# lpc11c14.net
KiCad netlist of a schematic drawn in Altium Designer
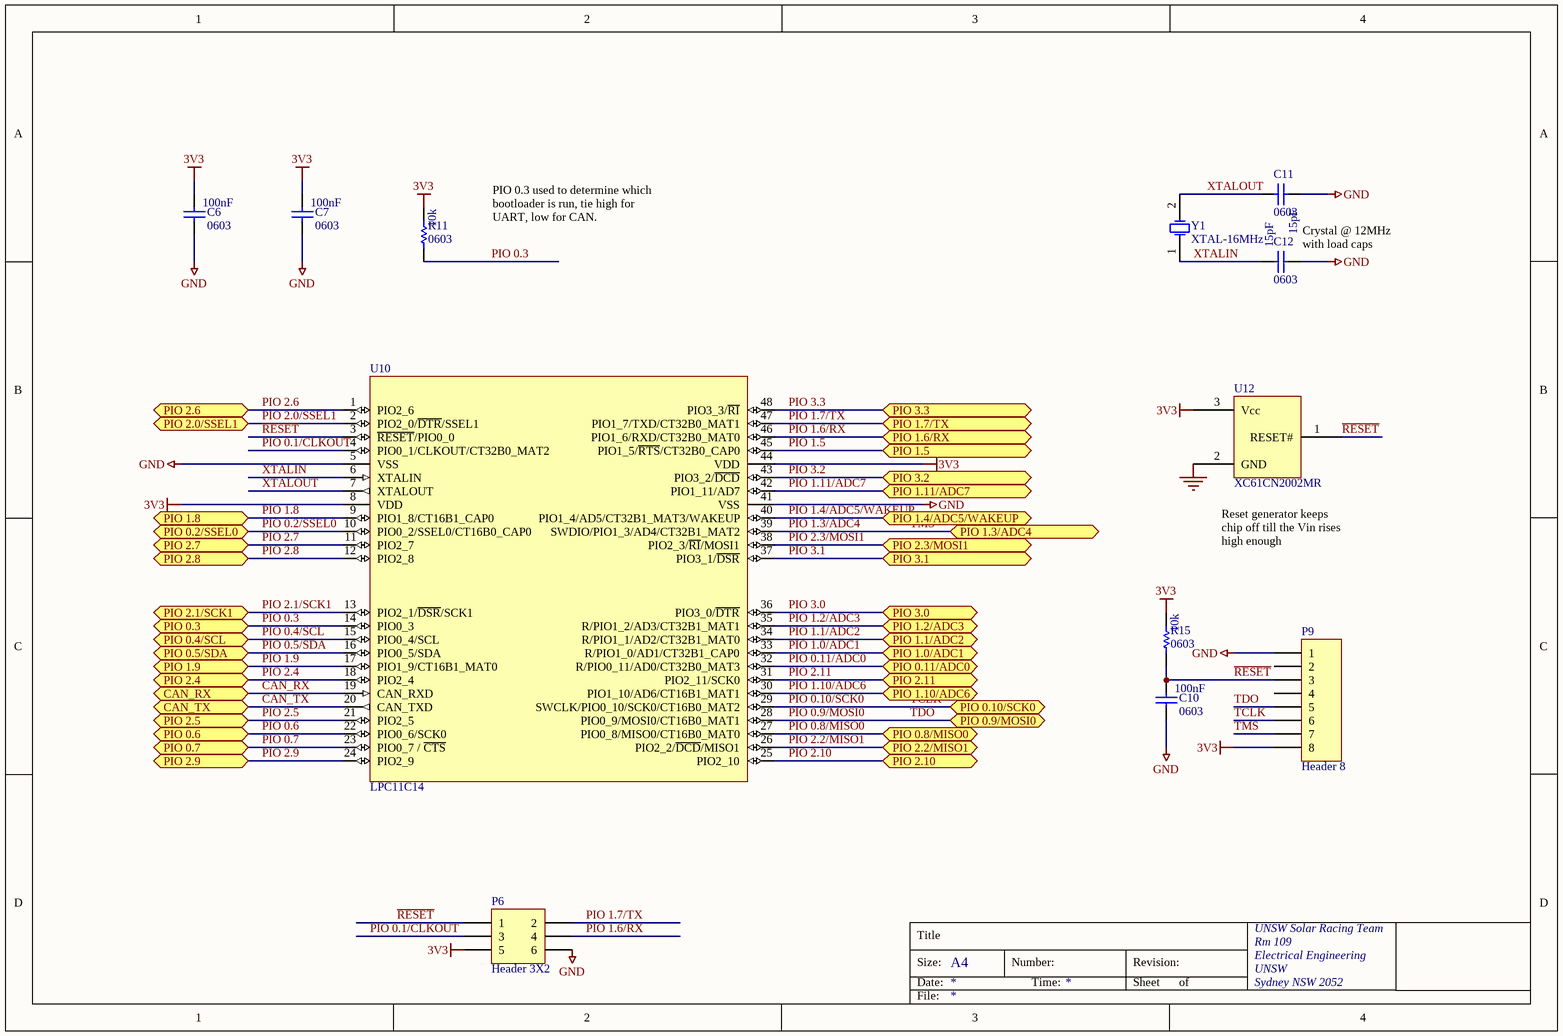
[diagram p0: lpc11c14.SchDoc]

(export (version "E")
  (design (tool "Eeschema 10.0.6"))
  (components
    (comp (ref "C6")
      (value "100nF")
      (footprint "0603_M")
      (description "Default Capacitor")
      (fields (field (name "PACKAGE") "0603") (field (name "Comment") "C"))
      (libsource (lib "UNSW_LIB") (part "C"))
    )
    (comp (ref "C7")
      (value "100nF")
      (footprint "0603_M")
      (description "Default Capacitor")
      (fields (field (name "PACKAGE") "0603") (field (name "Comment") "C"))
      (libsource (lib "UNSW_LIB") (part "C"))
    )
    (comp (ref "C10")
      (value "100nF")
      (footprint "0603_M")
      (description "Default Capacitor")
      (fields (field (name "PACKAGE") "0603") (field (name "Comment") "C"))
      (libsource (lib "UNSW_LIB") (part "C"))
    )
    (comp (ref "C11")
      (value "15pF")
      (footprint "0603_M")
      (description "Default Capacitor")
      (fields (field (name "PACKAGE") "0603") (field (name "Comment") "C"))
      (libsource (lib "UNSW_LIB") (part "C"))
    )
    (comp (ref "C12")
      (value "15pF")
      (footprint "0603_M")
      (description "Default Capacitor")
      (fields (field (name "PACKAGE") "0603") (field (name "Comment") "C"))
      (libsource (lib "UNSW_LIB") (part "C"))
    )
    (comp (ref "P6")
      (value "Header 3X2")
      (footprint "HDR2X3")
      (description "Header, 3-Pin, Dual row")
      (fields (field (name "PUBLISHER") "Altium Limited"))
      (libsource (lib "Miscellaneous Connectors") (part "Header 3X2"))
    )
    (comp (ref "P9")
      (value "Header 8")
      (footprint "HDR1X8")
      (description "Header, 8-Pin")
      (fields (field (name "PUBLISHER") "Altium Limited"))
      (libsource (lib "Miscellaneous Connectors") (part "Header 8"))
    )
    (comp (ref "R11")
      (value "10k")
      (footprint "0603_M")
      (description "Resistor")
      (fields (field (name "PACKAGE") "0603") (field (name "Comment") "R"))
      (libsource (lib "UNSW_LIB") (part "R"))
    )
    (comp (ref "R15")
      (value "10k")
      (footprint "0603_M")
      (description "Resistor")
      (fields (field (name "PACKAGE") "0603") (field (name "Comment") "R"))
      (libsource (lib "UNSW_LIB") (part "R"))
    )
    (comp (ref "U10")
      (value "LPC11C14")
      (footprint "QFP48")
      (description "NXP LPC11C14 Microcontroller")
      (libsource (lib "LPC") (part "LPC11C14_Full"))
    )
    (comp (ref "U12")
      (value "XC61CN2002MR")
      (footprint "SOT23-3")
      (description "SOT23 reset generator")
      (libsource (lib "*") (part "XC61F"))
    )
    (comp (ref "Y1")
      (value "XTAL-16MHz")
      (footprint "XTAL_TH_4.88MM")
      (description "Crystal Oscillator")
      (fields
        (field (name "MANUFACTURER") "NDK")
        (field (name "MANUFACTURER PART NUMBER") "NX5032GA-16.000000MHZ-LN-CD-1")
        (field (name "PUBLISHER") "Altium Limited")
      )
      (libsource (lib "UNSW_LIB") (part "XTAL-16MHz"))
    )
  )
  (nets
    (net (code "1") (name "/CAN_RX") (class "Default")
      (node (ref "U10") (pin "19") (pinfunction "CAN_RXD_19") (pintype "input"))
    )
    (net (code "2") (name "/CAN_TX") (class "Default")
      (node (ref "U10") (pin "20") (pinfunction "CAN_TXD_20") (pintype "output"))
    )
    (net (code "3") (name "/PIO 0.1{slash}CLKOUT") (class "Default")
      (node (ref "P6") (pin "3") (pinfunction "3_3") (pintype "passive"))
      (node (ref "U10") (pin "4") (pinfunction "PIO0_1/CLKOUT/CT32B0_MAT2_4") (pintype "bidirectional"))
    )
    (net (code "4") (name "/PIO 0.2{slash}SSEL0") (class "Default")
      (node (ref "U10") (pin "10") (pinfunction "PIO0_2/SSEL0/CT16B0_CAP0_10") (pintype "bidirectional"))
    )
    (net (code "5") (name "/PIO 0.3") (class "Default")
      (node (ref "R11") (pin "1") (pinfunction "1_1") (pintype "passive"))
      (node (ref "U10") (pin "14") (pinfunction "PIO0_3_14") (pintype "bidirectional"))
    )
    (net (code "6") (name "/PIO 0.4{slash}SCL") (class "Default")
      (node (ref "U10") (pin "15") (pinfunction "PIO0_4/SCL_15") (pintype "bidirectional"))
    )
    (net (code "7") (name "/PIO 0.5{slash}SDA") (class "Default")
      (node (ref "U10") (pin "16") (pinfunction "PIO0_5/SDA_16") (pintype "bidirectional"))
    )
    (net (code "8") (name "/PIO 0.6") (class "Default")
      (node (ref "U10") (pin "22") (pinfunction "PIO0_6/SCK0_22") (pintype "bidirectional"))
    )
    (net (code "9") (name "/PIO 0.7") (class "Default")
      (node (ref "U10") (pin "23") (pinfunction "PIO0_7_/_~{CTS}_23") (pintype "bidirectional"))
    )
    (net (code "10") (name "/PIO 0.8{slash}MISO0") (class "Default")
      (node (ref "U10") (pin "27") (pinfunction "PIO0_8/MISO0/CT16B0_MAT0_27") (pintype "bidirectional"))
    )
    (net (code "11") (name "/PIO 0.9{slash}MOSI0") (class "Default")
      (node (ref "P9") (pin "5") (pinfunction "5_5") (pintype "passive"))
      (node (ref "U10") (pin "28") (pinfunction "PIO0_9/MOSI0/CT16B0_MAT1_28") (pintype "bidirectional"))
    )
    (net (code "12") (name "/PIO 0.10{slash}SCK0") (class "Default")
      (node (ref "P9") (pin "6") (pinfunction "6_6") (pintype "passive"))
      (node (ref "U10") (pin "29") (pinfunction "SWCLK/PIO0_10/SCK0/CT16B0_MAT2_29") (pintype "bidirectional"))
    )
    (net (code "13") (name "/PIO 0.11{slash}ADC0") (class "Default")
      (node (ref "U10") (pin "32") (pinfunction "R/PIO0_11/AD0/CT32B0_MAT3_32") (pintype "bidirectional"))
    )
    (net (code "14") (name "/PIO 1.0{slash}ADC1") (class "Default")
      (node (ref "U10") (pin "33") (pinfunction "R/PIO1_0/AD1/CT32B1_CAP0_33") (pintype "bidirectional"))
    )
    (net (code "15") (name "/PIO 1.1{slash}ADC2") (class "Default")
      (node (ref "U10") (pin "34") (pinfunction "R/PIO1_1/AD2/CT32B1_MAT0_34") (pintype "bidirectional"))
    )
    (net (code "16") (name "/PIO 1.2{slash}ADC3") (class "Default")
      (node (ref "U10") (pin "35") (pinfunction "R/PIO1_2/AD3/CT32B1_MAT1_35") (pintype "bidirectional"))
    )
    (net (code "17") (name "/PIO 1.3{slash}ADC4") (class "Default")
      (node (ref "P9") (pin "7") (pinfunction "7_7") (pintype "passive"))
      (node (ref "U10") (pin "39") (pinfunction "SWDIO/PIO1_3/AD4/CT32B1_MAT2_39") (pintype "bidirectional"))
    )
    (net (code "18") (name "/PIO 1.4{slash}ADC5{slash}WAKEUP") (class "Default")
      (node (ref "U10") (pin "40") (pinfunction "PIO1_4/AD5/CT32B1_MAT3/WAKEUP_40") (pintype "bidirectional"))
    )
    (net (code "19") (name "/PIO 1.5") (class "Default")
      (node (ref "U10") (pin "45") (pinfunction "PIO1_5/~{RTS}/CT32B0_CAP0_45") (pintype "bidirectional"))
    )
    (net (code "20") (name "/PIO 1.6{slash}RX") (class "Default")
      (node (ref "P6") (pin "4") (pinfunction "4_4") (pintype "passive"))
      (node (ref "U10") (pin "46") (pinfunction "PIO1_6/RXD/CT32B0_MAT0_46") (pintype "bidirectional"))
    )
    (net (code "21") (name "/PIO 1.7{slash}TX") (class "Default")
      (node (ref "P6") (pin "2") (pinfunction "2_2") (pintype "passive"))
      (node (ref "U10") (pin "47") (pinfunction "PIO1_7/TXD/CT32B0_MAT1_47") (pintype "bidirectional"))
    )
    (net (code "22") (name "/PIO 1.8") (class "Default")
      (node (ref "U10") (pin "9") (pinfunction "PIO1_8/CT16B1_CAP0_9") (pintype "bidirectional"))
    )
    (net (code "23") (name "/PIO 1.9") (class "Default")
      (node (ref "U10") (pin "17") (pinfunction "PIO1_9/CT16B1_MAT0_17") (pintype "bidirectional"))
    )
    (net (code "24") (name "/PIO 1.10{slash}ADC6") (class "Default")
      (node (ref "U10") (pin "30") (pinfunction "PIO1_10/AD6/CT16B1_MAT1_30") (pintype "bidirectional"))
    )
    (net (code "25") (name "/PIO 1.11{slash}ADC7") (class "Default")
      (node (ref "U10") (pin "42") (pinfunction "PIO1_11/AD7_42") (pintype "bidirectional"))
    )
    (net (code "26") (name "/PIO 2.0{slash}SSEL1") (class "Default")
      (node (ref "U10") (pin "2") (pinfunction "PIO2_0/~{DTR}/SSEL1_2") (pintype "bidirectional"))
    )
    (net (code "27") (name "/PIO 2.1{slash}SCK1") (class "Default")
      (node (ref "U10") (pin "13") (pinfunction "PIO2_1/~{DSR}/SCK1_13") (pintype "bidirectional"))
    )
    (net (code "28") (name "/PIO 2.2{slash}MISO1") (class "Default")
      (node (ref "U10") (pin "26") (pinfunction "PIO2_2/~{DCD}/MISO1_26") (pintype "bidirectional"))
    )
    (net (code "29") (name "/PIO 2.3{slash}MOSI1") (class "Default")
      (node (ref "U10") (pin "38") (pinfunction "PIO2_3/~{RI}/MOSI1_38") (pintype "bidirectional"))
    )
    (net (code "30") (name "/PIO 2.4") (class "Default")
      (node (ref "U10") (pin "18") (pinfunction "PIO2_4_18") (pintype "bidirectional"))
    )
    (net (code "31") (name "/PIO 2.5") (class "Default")
      (node (ref "U10") (pin "21") (pinfunction "PIO2_5_21") (pintype "bidirectional"))
    )
    (net (code "32") (name "/PIO 2.6") (class "Default")
      (node (ref "U10") (pin "1") (pinfunction "PIO2_6_1") (pintype "bidirectional"))
    )
    (net (code "33") (name "/PIO 2.7") (class "Default")
      (node (ref "U10") (pin "11") (pinfunction "PIO2_7_11") (pintype "bidirectional"))
    )
    (net (code "34") (name "/PIO 2.8") (class "Default")
      (node (ref "U10") (pin "12") (pinfunction "PIO2_8_12") (pintype "bidirectional"))
    )
    (net (code "35") (name "/PIO 2.9") (class "Default")
      (node (ref "U10") (pin "24") (pinfunction "PIO2_9_24") (pintype "bidirectional"))
    )
    (net (code "36") (name "/PIO 2.10") (class "Default")
      (node (ref "U10") (pin "25") (pinfunction "PIO2_10_25") (pintype "bidirectional"))
    )
    (net (code "37") (name "/PIO 2.11") (class "Default")
      (node (ref "U10") (pin "31") (pinfunction "PIO2_11/SCK0_31") (pintype "bidirectional"))
    )
    (net (code "38") (name "/PIO 3.0") (class "Default")
      (node (ref "U10") (pin "36") (pinfunction "PIO3_0/~{DTR}_36") (pintype "bidirectional"))
    )
    (net (code "39") (name "/PIO 3.1") (class "Default")
      (node (ref "U10") (pin "37") (pinfunction "PIO3_1/~{DSR}_37") (pintype "bidirectional"))
    )
    (net (code "40") (name "/PIO 3.2") (class "Default")
      (node (ref "U10") (pin "43") (pinfunction "PIO3_2/~{DCD}_43") (pintype "bidirectional"))
    )
    (net (code "41") (name "/PIO 3.3") (class "Default")
      (node (ref "U10") (pin "48") (pinfunction "PIO3_3/~{RI}_48") (pintype "bidirectional"))
    )
    (net (code "42") (name "/XTALIN") (class "Default")
      (node (ref "C12") (pin "1") (pinfunction "1_1") (pintype "passive"))
      (node (ref "U10") (pin "6") (pinfunction "XTALIN_6") (pintype "input"))
      (node (ref "Y1") (pin "1") (pinfunction "OSC1_1") (pintype "passive"))
    )
    (net (code "43") (name "/XTALOUT") (class "Default")
      (node (ref "C11") (pin "2") (pinfunction "2_2") (pintype "passive"))
      (node (ref "U10") (pin "7") (pinfunction "XTALOUT_7") (pintype "output"))
      (node (ref "Y1") (pin "2") (pinfunction "OSC2_2") (pintype "passive"))
    )
    (net (code "44") (name "/~{RESET}") (class "Default")
      (node (ref "C10") (pin "1") (pinfunction "1_1") (pintype "passive"))
      (node (ref "P6") (pin "1") (pinfunction "1_1") (pintype "passive"))
      (node (ref "P9") (pin "3") (pinfunction "3_3") (pintype "passive"))
      (node (ref "R15") (pin "1") (pinfunction "1_1") (pintype "passive"))
      (node (ref "U10") (pin "3") (pinfunction "~{RESET}/PIO0_0_3") (pintype "bidirectional"))
      (node (ref "U12") (pin "1") (pinfunction "RESET#_1") (pintype "passive"))
    )
    (net (code "45") (name "3V3") (class "Default")
      (node (ref "C6") (pin "1") (pinfunction "1_1") (pintype "passive"))
      (node (ref "C7") (pin "1") (pinfunction "1_1") (pintype "passive"))
      (node (ref "P6") (pin "5") (pinfunction "5_5") (pintype "passive"))
      (node (ref "P9") (pin "8") (pinfunction "8_8") (pintype "passive"))
      (node (ref "R11") (pin "2") (pinfunction "2_2") (pintype "passive"))
      (node (ref "R15") (pin "2") (pinfunction "2_2") (pintype "passive"))
      (node (ref "U10") (pin "44") (pinfunction "VDD_44") (pintype "power_in"))
      (node (ref "U10") (pin "8") (pinfunction "VDD_8") (pintype "power_in"))
      (node (ref "U12") (pin "3") (pinfunction "Vcc_3") (pintype "passive"))
    )
    (net (code "46") (name "GND") (class "Default")
      (node (ref "C10") (pin "2") (pinfunction "2_2") (pintype "passive"))
      (node (ref "C11") (pin "1") (pinfunction "1_1") (pintype "passive"))
      (node (ref "C12") (pin "2") (pinfunction "2_2") (pintype "passive"))
      (node (ref "C6") (pin "2") (pinfunction "2_2") (pintype "passive"))
      (node (ref "C7") (pin "2") (pinfunction "2_2") (pintype "passive"))
      (node (ref "P6") (pin "6") (pinfunction "6_6") (pintype "passive"))
      (node (ref "P9") (pin "1") (pinfunction "1_1") (pintype "passive"))
      (node (ref "U10") (pin "41") (pinfunction "VSS_41") (pintype "power_in"))
      (node (ref "U10") (pin "5") (pinfunction "VSS_5") (pintype "power_in"))
      (node (ref "U12") (pin "2") (pinfunction "GND_2") (pintype "passive"))
    )
    (net (code "47") (name "unconnected-(P9-Pad2)") (class "Default")
      (node (ref "P9") (pin "2") (pinfunction "2_2") (pintype "passive"))
    )
    (net (code "48") (name "unconnected-(P9-Pad4)") (class "Default")
      (node (ref "P9") (pin "4") (pinfunction "4_4") (pintype "passive"))
    )
  )
)
